# 08-DIPSwitches_I2C.net
KiCad netlist of a schematic drawn in Altium Designer
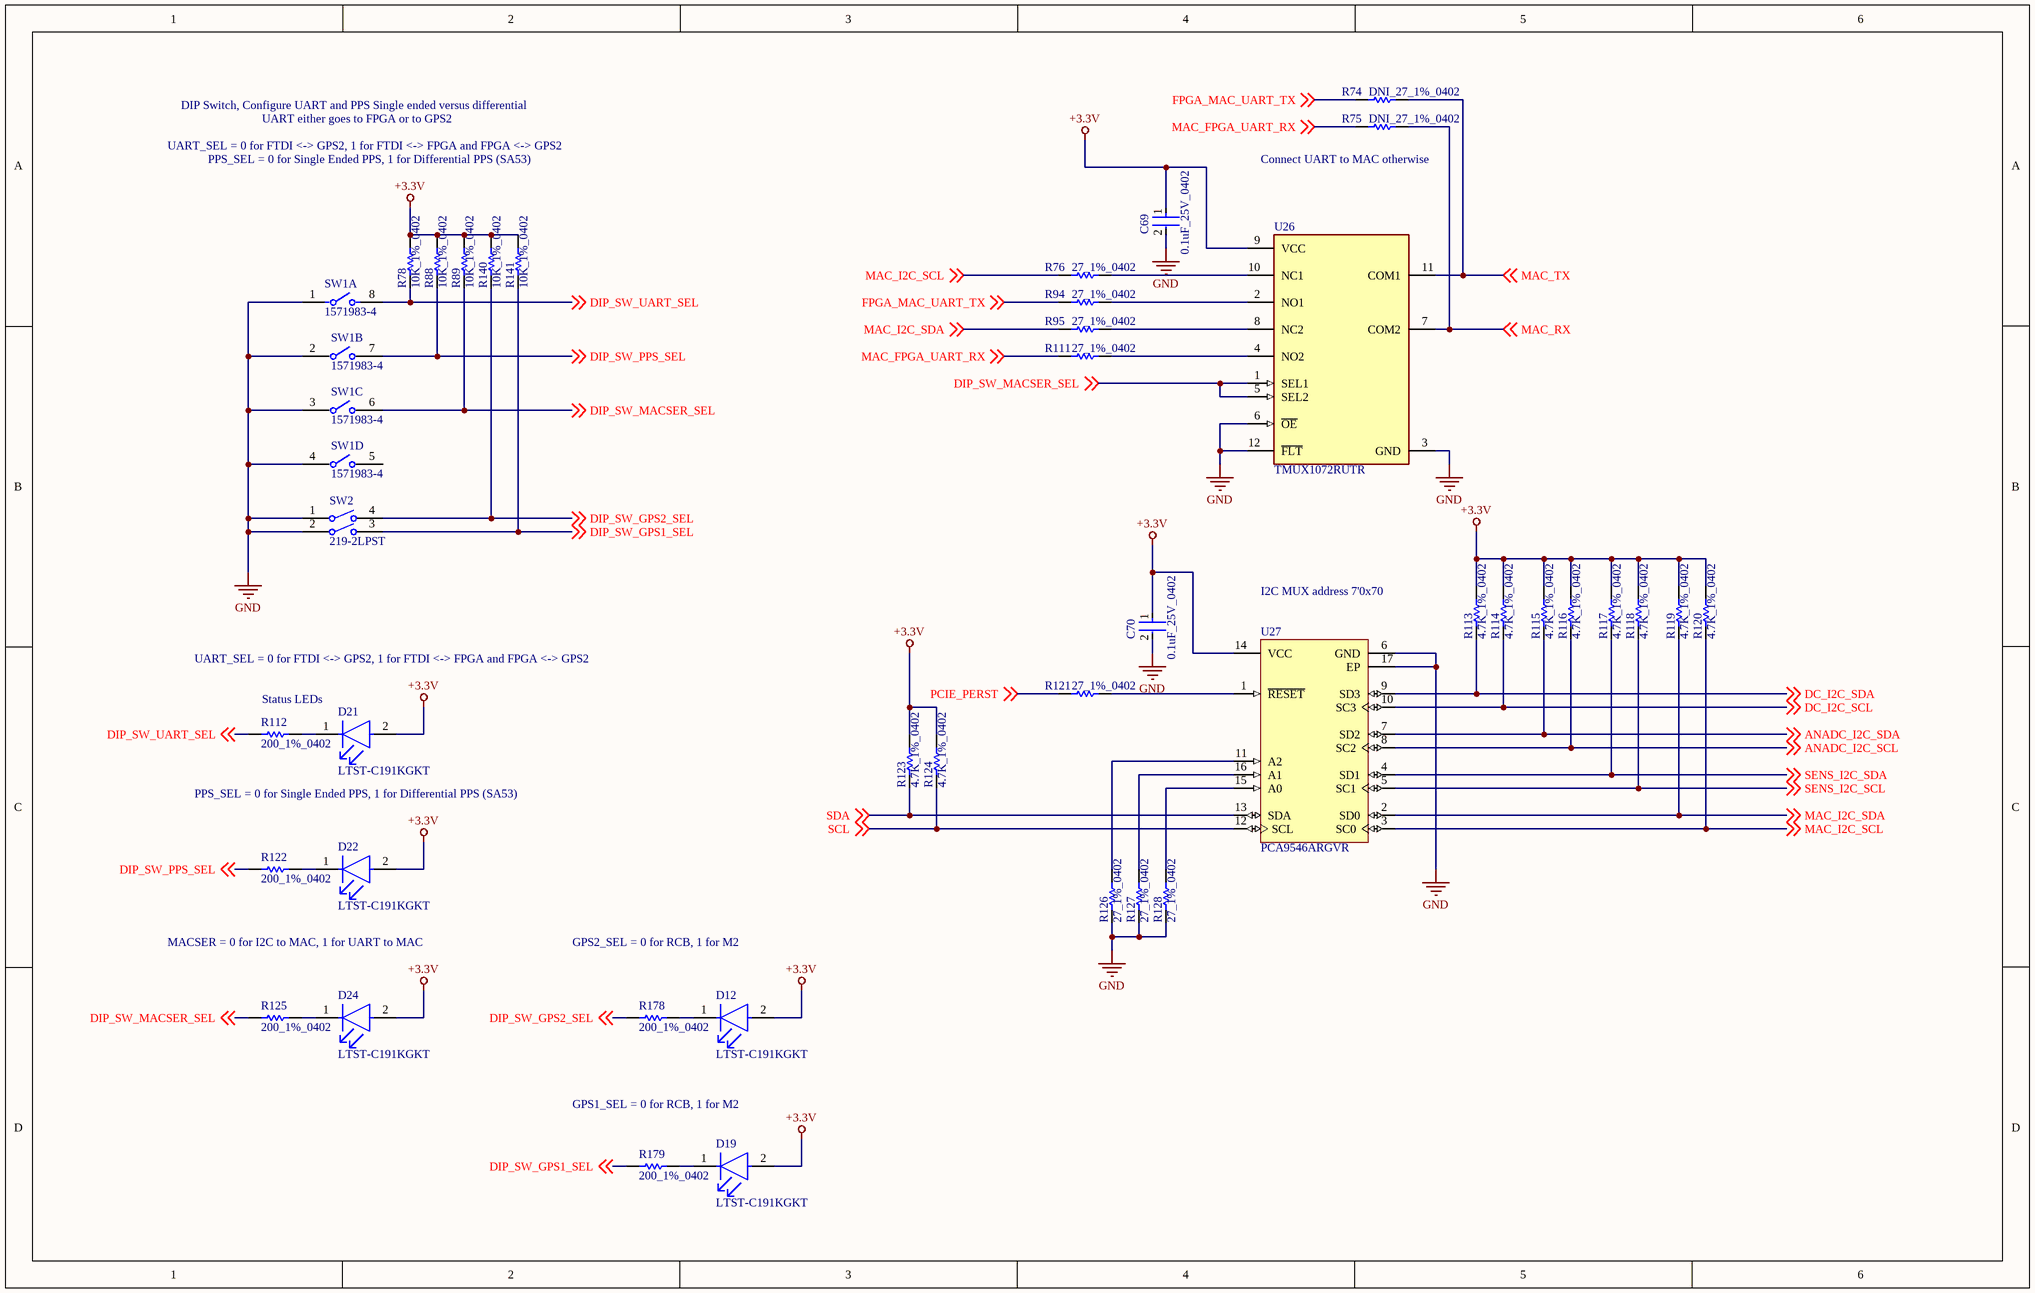
[diagram p0: 08-DIPSwitches_I2C.SchDoc]

(export (version "E")
  (design (tool "Eeschema 10.0.6"))
  (components
    (comp (ref "C69")
      (value "0.1uF_25V_0402")
      (footprint "FP-0402-L_1_0_1-W_0_5_0_1-IPC_C")
      (description "General Purpose Ceramic Capacitor, 0402, 100nF, 10%, X7R, 15%, 25V")
      (fields (field (name "VOLTAGE") "25V") (field (name "TOLERANCE") "10%"))
      (libsource (lib "Altium Content Vault") (part "b4654b650e69147ec39a6b967a45e02"))
    )
    (comp (ref "C70")
      (value "0.1uF_25V_0402")
      (footprint "FP-0402-L_1_0_1-W_0_5_0_1-IPC_C")
      (description "General Purpose Ceramic Capacitor, 0402, 100nF, 10%, X7R, 15%, 25V")
      (fields (field (name "VOLTAGE") "25V") (field (name "TOLERANCE") "10%"))
      (libsource (lib "Altium Content Vault") (part "b4654b650e69147ec39a6b967a45e02"))
    )
    (comp (ref "D12")
      (value "LTST-C191KGKT")
      (footprint "FP-LTST-C191KGKT-MFG")
      (description "LED GREEN CLEAR SMD")
      (libsource (lib "Altium Content Vault") (part "8706943c75ba83719d021d2fdc84c58"))
    )
    (comp (ref "D19")
      (value "LTST-C191KGKT")
      (footprint "FP-LTST-C191KGKT-MFG")
      (description "LED GREEN CLEAR SMD")
      (libsource (lib "Altium Content Vault") (part "8706943c75ba83719d021d2fdc84c58"))
    )
    (comp (ref "D21")
      (value "LTST-C191KGKT")
      (footprint "FP-LTST-C191KGKT-MFG")
      (description "LED GREEN CLEAR SMD")
      (libsource (lib "Altium Content Vault") (part "8706943c75ba83719d021d2fdc84c58"))
    )
    (comp (ref "D22")
      (value "LTST-C191KGKT")
      (footprint "FP-LTST-C191KGKT-MFG")
      (description "LED GREEN CLEAR SMD")
      (libsource (lib "Altium Content Vault") (part "8706943c75ba83719d021d2fdc84c58"))
    )
    (comp (ref "D24")
      (value "LTST-C191KGKT")
      (footprint "FP-LTST-C191KGKT-MFG")
      (description "LED GREEN CLEAR SMD")
      (libsource (lib "Altium Content Vault") (part "8706943c75ba83719d021d2fdc84c58"))
    )
    (comp (ref "R74")
      (value "DNI_27_1%_0402")
      (footprint "RESC1005X40X25NL05T05")
      (fields (field (name "PART NUMBER") "CRCW040227R0FKED") (field (name "MANUFACTURER") "Vishay Dale"))
      (libsource (lib "Altium Content Vault") (part "RES"))
    )
    (comp (ref "R75")
      (value "DNI_27_1%_0402")
      (footprint "RESC1005X40X25NL05T05")
      (fields (field (name "PART NUMBER") "CRCW040227R0FKED") (field (name "MANUFACTURER") "Vishay Dale"))
      (libsource (lib "Altium Content Vault") (part "RES"))
    )
    (comp (ref "R76")
      (value "27_1%_0402")
      (footprint "RESC1005X40X25NL05T05")
      (fields (field (name "PART NUMBER") "CRCW040227R0FKED") (field (name "MANUFACTURER") "Vishay Dale"))
      (libsource (lib "Altium Content Vault") (part "RES"))
    )
    (comp (ref "R78")
      (value "10K_1%_0402")
      (footprint "RESC1005X40X25LL05T10")
      (fields (field (name "PART NUMBER") "RC0402FR-0710KL") (field (name "MANUFACTURER") "Yageo / Phycomp"))
      (libsource (lib "Altium Content Vault") (part "RES"))
    )
    (comp (ref "R88")
      (value "10K_1%_0402")
      (footprint "RESC1005X40X25LL05T10")
      (fields (field (name "PART NUMBER") "RC0402FR-0710KL") (field (name "MANUFACTURER") "Yageo / Phycomp"))
      (libsource (lib "Altium Content Vault") (part "RES"))
    )
    (comp (ref "R89")
      (value "10K_1%_0402")
      (footprint "RESC1005X40X25LL05T10")
      (fields (field (name "PART NUMBER") "RC0402FR-0710KL") (field (name "MANUFACTURER") "Yageo / Phycomp"))
      (libsource (lib "Altium Content Vault") (part "RES"))
    )
    (comp (ref "R94")
      (value "27_1%_0402")
      (footprint "RESC1005X40X25NL05T05")
      (fields (field (name "PART NUMBER") "CRCW040227R0FKED") (field (name "MANUFACTURER") "Vishay Dale"))
      (libsource (lib "Altium Content Vault") (part "RES"))
    )
    (comp (ref "R95")
      (value "27_1%_0402")
      (footprint "RESC1005X40X25NL05T05")
      (fields (field (name "PART NUMBER") "CRCW040227R0FKED") (field (name "MANUFACTURER") "Vishay Dale"))
      (libsource (lib "Altium Content Vault") (part "RES"))
    )
    (comp (ref "R111")
      (value "27_1%_0402")
      (footprint "RESC1005X40X25NL05T05")
      (fields (field (name "PART NUMBER") "CRCW040227R0FKED") (field (name "MANUFACTURER") "Vishay Dale"))
      (libsource (lib "Altium Content Vault") (part "RES"))
    )
    (comp (ref "R112")
      (value "200_1%_0402")
      (footprint "RESC1005X40X25NL05T05")
      (fields (field (name "MANUFACTURER") "Vishay Dale") (field (name "PART NUMBER") "CRCW0402200RFKTD"))
      (libsource (lib "Altium Content Vault") (part "RES"))
    )
    (comp (ref "R113")
      (value "4.7K_1%_0402")
      (footprint "RESC1005X40X25NL10T10")
      (fields (field (name "MANUFACTURER") "Bourns") (field (name "PART NUMBER") "CR0402-FX-4701GLF"))
      (libsource (lib "Altium Content Vault") (part "RES"))
    )
    (comp (ref "R114")
      (value "4.7K_1%_0402")
      (footprint "RESC1005X40X25NL10T10")
      (fields (field (name "MANUFACTURER") "Bourns") (field (name "PART NUMBER") "CR0402-FX-4701GLF"))
      (libsource (lib "Altium Content Vault") (part "RES"))
    )
    (comp (ref "R115")
      (value "4.7K_1%_0402")
      (footprint "RESC1005X40X25NL10T10")
      (fields (field (name "MANUFACTURER") "Bourns") (field (name "PART NUMBER") "CR0402-FX-4701GLF"))
      (libsource (lib "Altium Content Vault") (part "RES"))
    )
    (comp (ref "R116")
      (value "4.7K_1%_0402")
      (footprint "RESC1005X40X25NL10T10")
      (fields (field (name "MANUFACTURER") "Bourns") (field (name "PART NUMBER") "CR0402-FX-4701GLF"))
      (libsource (lib "Altium Content Vault") (part "RES"))
    )
    (comp (ref "R117")
      (value "4.7K_1%_0402")
      (footprint "RESC1005X40X25NL10T10")
      (fields (field (name "MANUFACTURER") "Bourns") (field (name "PART NUMBER") "CR0402-FX-4701GLF"))
      (libsource (lib "Altium Content Vault") (part "RES"))
    )
    (comp (ref "R118")
      (value "4.7K_1%_0402")
      (footprint "RESC1005X40X25NL10T10")
      (fields (field (name "MANUFACTURER") "Bourns") (field (name "PART NUMBER") "CR0402-FX-4701GLF"))
      (libsource (lib "Altium Content Vault") (part "RES"))
    )
    (comp (ref "R119")
      (value "4.7K_1%_0402")
      (footprint "RESC1005X40X25NL10T10")
      (fields (field (name "MANUFACTURER") "Bourns") (field (name "PART NUMBER") "CR0402-FX-4701GLF"))
      (libsource (lib "Altium Content Vault") (part "RES"))
    )
    (comp (ref "R120")
      (value "4.7K_1%_0402")
      (footprint "RESC1005X40X25NL10T10")
      (fields (field (name "MANUFACTURER") "Bourns") (field (name "PART NUMBER") "CR0402-FX-4701GLF"))
      (libsource (lib "Altium Content Vault") (part "RES"))
    )
    (comp (ref "R121")
      (value "27_1%_0402")
      (footprint "RESC1005X40X25NL05T05")
      (fields (field (name "PART NUMBER") "CRCW040227R0FKED") (field (name "MANUFACTURER") "Vishay Dale"))
      (libsource (lib "Altium Content Vault") (part "RES"))
    )
    (comp (ref "R122")
      (value "200_1%_0402")
      (footprint "RESC1005X40X25NL05T05")
      (fields (field (name "MANUFACTURER") "Vishay Dale") (field (name "PART NUMBER") "CRCW0402200RFKTD"))
      (libsource (lib "Altium Content Vault") (part "RES"))
    )
    (comp (ref "R123")
      (value "4.7K_1%_0402")
      (footprint "RESC1005X40X25NL10T10")
      (fields (field (name "MANUFACTURER") "Bourns") (field (name "PART NUMBER") "CR0402-FX-4701GLF"))
      (libsource (lib "Altium Content Vault") (part "RES"))
    )
    (comp (ref "R124")
      (value "4.7K_1%_0402")
      (footprint "RESC1005X40X25NL10T10")
      (fields (field (name "MANUFACTURER") "Bourns") (field (name "PART NUMBER") "CR0402-FX-4701GLF"))
      (libsource (lib "Altium Content Vault") (part "RES"))
    )
    (comp (ref "R125")
      (value "200_1%_0402")
      (footprint "RESC1005X40X25NL05T05")
      (fields (field (name "MANUFACTURER") "Vishay Dale") (field (name "PART NUMBER") "CRCW0402200RFKTD"))
      (libsource (lib "Altium Content Vault") (part "RES"))
    )
    (comp (ref "R126")
      (value "27_1%_0402")
      (footprint "RESC1005X40X25NL05T05")
      (fields (field (name "PART NUMBER") "CRCW040227R0FKED") (field (name "MANUFACTURER") "Vishay Dale"))
      (libsource (lib "Altium Content Vault") (part "RES"))
    )
    (comp (ref "R127")
      (value "27_1%_0402")
      (footprint "RESC1005X40X25NL05T05")
      (fields (field (name "PART NUMBER") "CRCW040227R0FKED") (field (name "MANUFACTURER") "Vishay Dale"))
      (libsource (lib "Altium Content Vault") (part "RES"))
    )
    (comp (ref "R128")
      (value "27_1%_0402")
      (footprint "RESC1005X40X25NL05T05")
      (fields (field (name "PART NUMBER") "CRCW040227R0FKED") (field (name "MANUFACTURER") "Vishay Dale"))
      (libsource (lib "Altium Content Vault") (part "RES"))
    )
    (comp (ref "R140")
      (value "10K_1%_0402")
      (footprint "RESC1005X40X25LL05T10")
      (fields (field (name "PART NUMBER") "RC0402FR-0710KL") (field (name "MANUFACTURER") "Yageo / Phycomp"))
      (libsource (lib "Altium Content Vault") (part "RES"))
    )
    (comp (ref "R141")
      (value "10K_1%_0402")
      (footprint "RESC1005X40X25LL05T10")
      (fields (field (name "PART NUMBER") "RC0402FR-0710KL") (field (name "MANUFACTURER") "Yageo / Phycomp"))
      (libsource (lib "Altium Content Vault") (part "RES"))
    )
    (comp (ref "R178")
      (value "200_1%_0402")
      (footprint "RESC1005X40X25NL05T05")
      (fields (field (name "MANUFACTURER") "Vishay Dale") (field (name "PART NUMBER") "CRCW0402200RFKTD"))
      (libsource (lib "Altium Content Vault") (part "RES"))
    )
    (comp (ref "R179")
      (value "200_1%_0402")
      (footprint "RESC1005X40X25NL05T05")
      (fields (field (name "MANUFACTURER") "Vishay Dale") (field (name "PART NUMBER") "CRCW0402200RFKTD"))
      (libsource (lib "Altium Content Vault") (part "RES"))
    )
    (comp (ref "SW1")
      (value "1571983-4")
      (footprint "FP-1571983-4-MFG")
      (description "SWITCH SLIDE DIP SPST 25MA 24V")
      (fields
        (field (name "OCTOPART") "https://octopart.com/1571983-4-te+connectivity-46507521")
        (field (name "MANUFACTURER") "TE Connectivity")
      )
      (libsource (lib "Altium Content Vault") (part "6123b3bffd52fd60b6df23d79e332fa"))
    )
    (comp (ref "SW2")
      (value "219-2LPST")
      (footprint "CTS-219-2LPST_V")
      (description "Surface Mount DIP Switch Auto Placeable, -55 to 85 degC, 4-Pin SMD, RoHS, Tube")
      (fields (field (name "MANUFACTURER") "CTS Corporation"))
      (libsource (lib "Altium Content Vault") (part "SW-SPST-4_C"))
    )
    (comp (ref "U26")
      (value "TMUX1072RUTR")
      (footprint "FP-RUT0012A-MFG")
      (description "IC SWITCH SPDT DUAL 12UQFN")
      (libsource (lib "Altium Content Vault") (part "12a319ab100cd6cfe745e35972674f5"))
    )
    (comp (ref "U27")
      (value "PCA9546ARGVR")
      (footprint "RGV0016A_V")
      (fields (field (name "MANUFACTURER") "Texas Instruments"))
      (libsource (lib "Altium Content Vault") (part "TI-PCA9546A-VQFN_RGV-16"))
    )
  )
  (nets
    (net (code "1") (name "+3.3V") (class "Default")
      (node (ref "C69") (pin "1") (pinfunction "1_1") (pintype "passive"))
      (node (ref "C70") (pin "1") (pinfunction "1_1") (pintype "passive"))
      (node (ref "D12") (pin "2") (pinfunction "A_2") (pintype "passive"))
      (node (ref "D19") (pin "2") (pinfunction "A_2") (pintype "passive"))
      (node (ref "D21") (pin "2") (pinfunction "A_2") (pintype "passive"))
      (node (ref "D22") (pin "2") (pinfunction "A_2") (pintype "passive"))
      (node (ref "D24") (pin "2") (pinfunction "A_2") (pintype "passive"))
      (node (ref "R113") (pin "2") (pinfunction "2_2") (pintype "passive"))
      (node (ref "R114") (pin "2") (pinfunction "2_2") (pintype "passive"))
      (node (ref "R115") (pin "2") (pinfunction "2_2") (pintype "passive"))
      (node (ref "R116") (pin "2") (pinfunction "2_2") (pintype "passive"))
      (node (ref "R117") (pin "2") (pinfunction "2_2") (pintype "passive"))
      (node (ref "R118") (pin "2") (pinfunction "2_2") (pintype "passive"))
      (node (ref "R119") (pin "2") (pinfunction "2_2") (pintype "passive"))
      (node (ref "R120") (pin "2") (pinfunction "2_2") (pintype "passive"))
      (node (ref "R123") (pin "2") (pinfunction "2_2") (pintype "passive"))
      (node (ref "R124") (pin "2") (pinfunction "2_2") (pintype "passive"))
      (node (ref "R140") (pin "1") (pinfunction "1_1") (pintype "passive"))
      (node (ref "R141") (pin "1") (pinfunction "1_1") (pintype "passive"))
      (node (ref "R78") (pin "1") (pinfunction "1_1") (pintype "passive"))
      (node (ref "R88") (pin "1") (pinfunction "1_1") (pintype "passive"))
      (node (ref "R89") (pin "1") (pinfunction "1_1") (pintype "passive"))
      (node (ref "U26") (pin "9") (pinfunction "VCC_9") (pintype "power_in"))
      (node (ref "U27") (pin "14") (pinfunction "VCC_14") (pintype "power_in"))
    )
    (net (code "2") (name "ANADC_I2C_SCL") (class "Default")
      (node (ref "R116") (pin "1") (pinfunction "1_1") (pintype "passive"))
      (node (ref "U27") (pin "8") (pinfunction "SC2_8") (pintype "bidirectional"))
    )
    (net (code "3") (name "ANADC_I2C_SDA") (class "Default")
      (node (ref "R115") (pin "1") (pinfunction "1_1") (pintype "passive"))
      (node (ref "U27") (pin "7") (pinfunction "SD2_7") (pintype "bidirectional"))
    )
    (net (code "4") (name "DC_I2C_SCL") (class "Default")
      (node (ref "R114") (pin "1") (pinfunction "1_1") (pintype "passive"))
      (node (ref "U27") (pin "10") (pinfunction "SC3_10") (pintype "bidirectional"))
    )
    (net (code "5") (name "DC_I2C_SDA") (class "Default")
      (node (ref "R113") (pin "1") (pinfunction "1_1") (pintype "passive"))
      (node (ref "U27") (pin "9") (pinfunction "SD3_9") (pintype "bidirectional"))
    )
    (net (code "6") (name "DIP_SW_GPS1_SEL") (class "Default")
      (node (ref "R141") (pin "2") (pinfunction "2_2") (pintype "passive"))
      (node (ref "R179") (pin "2") (pinfunction "2_2") (pintype "passive"))
      (node (ref "SW2") (pin "3") (pinfunction "3_3") (pintype "passive"))
    )
    (net (code "7") (name "DIP_SW_GPS2_SEL") (class "Default")
      (node (ref "R140") (pin "2") (pinfunction "2_2") (pintype "passive"))
      (node (ref "R178") (pin "2") (pinfunction "2_2") (pintype "passive"))
      (node (ref "SW2") (pin "4") (pinfunction "4_4") (pintype "passive"))
    )
    (net (code "8") (name "DIP_SW_MACSER_SEL") (class "Default")
      (node (ref "R125") (pin "2") (pinfunction "2_2") (pintype "passive"))
      (node (ref "R89") (pin "2") (pinfunction "2_2") (pintype "passive"))
      (node (ref "SW1") (pin "6") (pinfunction "6_6") (pintype "passive"))
      (node (ref "U26") (pin "1") (pinfunction "SEL1_1") (pintype "input"))
      (node (ref "U26") (pin "5") (pinfunction "SEL2_5") (pintype "input"))
    )
    (net (code "9") (name "DIP_SW_PPS_SEL") (class "Default")
      (node (ref "R122") (pin "2") (pinfunction "2_2") (pintype "passive"))
      (node (ref "R88") (pin "2") (pinfunction "2_2") (pintype "passive"))
      (node (ref "SW1") (pin "7") (pinfunction "7_7") (pintype "passive"))
    )
    (net (code "10") (name "DIP_SW_UART_SEL") (class "Default")
      (node (ref "R112") (pin "2") (pinfunction "2_2") (pintype "passive"))
      (node (ref "R78") (pin "2") (pinfunction "2_2") (pintype "passive"))
      (node (ref "SW1") (pin "8") (pinfunction "8_8") (pintype "passive"))
    )
    (net (code "11") (name "FPGA_MAC_UART_TX") (class "Default")
      (node (ref "R74") (pin "1") (pinfunction "1_1") (pintype "passive"))
      (node (ref "R94") (pin "1") (pinfunction "1_1") (pintype "passive"))
    )
    (net (code "12") (name "GND") (class "Default")
      (node (ref "C69") (pin "2") (pinfunction "2_2") (pintype "passive"))
      (node (ref "C70") (pin "2") (pinfunction "2_2") (pintype "passive"))
      (node (ref "R126") (pin "1") (pinfunction "1_1") (pintype "passive"))
      (node (ref "R127") (pin "1") (pinfunction "1_1") (pintype "passive"))
      (node (ref "R128") (pin "1") (pinfunction "1_1") (pintype "passive"))
      (node (ref "SW1") (pin "1") (pinfunction "1_1") (pintype "passive"))
      (node (ref "SW1") (pin "2") (pinfunction "2_2") (pintype "passive"))
      (node (ref "SW1") (pin "3") (pinfunction "3_3") (pintype "passive"))
      (node (ref "SW1") (pin "4") (pinfunction "4_4") (pintype "passive"))
      (node (ref "SW2") (pin "1") (pinfunction "1_1") (pintype "passive"))
      (node (ref "SW2") (pin "2") (pinfunction "2_2") (pintype "passive"))
      (node (ref "U26") (pin "12") (pinfunction "~{FLT}_12") (pintype "open_collector"))
      (node (ref "U26") (pin "3") (pinfunction "GND_3") (pintype "power_in"))
      (node (ref "U26") (pin "6") (pinfunction "~{OE}_6") (pintype "input"))
      (node (ref "U27") (pin "17") (pinfunction "EP_17") (pintype "passive"))
      (node (ref "U27") (pin "6") (pinfunction "GND_6") (pintype "power_in"))
    )
    (net (code "13") (name "MAC_FPGA_UART_RX") (class "Default")
      (node (ref "R111") (pin "1") (pinfunction "1_1") (pintype "passive"))
      (node (ref "R75") (pin "1") (pinfunction "1_1") (pintype "passive"))
    )
    (net (code "14") (name "MAC_I2C_SCL") (class "Default")
      (node (ref "R120") (pin "1") (pinfunction "1_1") (pintype "passive"))
      (node (ref "R76") (pin "1") (pinfunction "1_1") (pintype "passive"))
      (node (ref "U27") (pin "3") (pinfunction "SC0_3") (pintype "bidirectional"))
    )
    (net (code "15") (name "MAC_I2C_SDA") (class "Default")
      (node (ref "R119") (pin "1") (pinfunction "1_1") (pintype "passive"))
      (node (ref "R95") (pin "1") (pinfunction "1_1") (pintype "passive"))
      (node (ref "U27") (pin "2") (pinfunction "SD0_2") (pintype "bidirectional"))
    )
    (net (code "16") (name "MAC_RX") (class "Default")
      (node (ref "R75") (pin "2") (pinfunction "2_2") (pintype "passive"))
      (node (ref "U26") (pin "7") (pinfunction "COM2_7") (pintype "passive"))
    )
    (net (code "17") (name "MAC_TX") (class "Default")
      (node (ref "R74") (pin "2") (pinfunction "2_2") (pintype "passive"))
      (node (ref "U26") (pin "11") (pinfunction "COM1_11") (pintype "passive"))
    )
    (net (code "18") (name "Net-(D12-C)") (class "Default")
      (node (ref "D12") (pin "1") (pinfunction "C_1") (pintype "passive"))
      (node (ref "R178") (pin "1") (pinfunction "1_1") (pintype "passive"))
    )
    (net (code "19") (name "Net-(D19-C)") (class "Default")
      (node (ref "D19") (pin "1") (pinfunction "C_1") (pintype "passive"))
      (node (ref "R179") (pin "1") (pinfunction "1_1") (pintype "passive"))
    )
    (net (code "20") (name "Net-(D21-C)") (class "Default")
      (node (ref "D21") (pin "1") (pinfunction "C_1") (pintype "passive"))
      (node (ref "R112") (pin "1") (pinfunction "1_1") (pintype "passive"))
    )
    (net (code "21") (name "Net-(D22-C)") (class "Default")
      (node (ref "D22") (pin "1") (pinfunction "C_1") (pintype "passive"))
      (node (ref "R122") (pin "1") (pinfunction "1_1") (pintype "passive"))
    )
    (net (code "22") (name "Net-(D24-C)") (class "Default")
      (node (ref "D24") (pin "1") (pinfunction "C_1") (pintype "passive"))
      (node (ref "R125") (pin "1") (pinfunction "1_1") (pintype "passive"))
    )
    (net (code "23") (name "Net-(U26-NC1)") (class "Default")
      (node (ref "R76") (pin "2") (pinfunction "2_2") (pintype "passive"))
      (node (ref "U26") (pin "10") (pinfunction "NC1_10") (pintype "passive"))
    )
    (net (code "24") (name "Net-(U26-NC2)") (class "Default")
      (node (ref "R95") (pin "2") (pinfunction "2_2") (pintype "passive"))
      (node (ref "U26") (pin "8") (pinfunction "NC2_8") (pintype "passive"))
    )
    (net (code "25") (name "Net-(U26-NO1)") (class "Default")
      (node (ref "R94") (pin "2") (pinfunction "2_2") (pintype "passive"))
      (node (ref "U26") (pin "2") (pinfunction "NO1_2") (pintype "passive"))
    )
    (net (code "26") (name "Net-(U26-NO2)") (class "Default")
      (node (ref "R111") (pin "2") (pinfunction "2_2") (pintype "passive"))
      (node (ref "U26") (pin "4") (pinfunction "NO2_4") (pintype "passive"))
    )
    (net (code "27") (name "Net-(U27-A0)") (class "Default")
      (node (ref "R128") (pin "2") (pinfunction "2_2") (pintype "passive"))
      (node (ref "U27") (pin "15") (pinfunction "A0_15") (pintype "input"))
    )
    (net (code "28") (name "Net-(U27-A1)") (class "Default")
      (node (ref "R127") (pin "2") (pinfunction "2_2") (pintype "passive"))
      (node (ref "U27") (pin "16") (pinfunction "A1_16") (pintype "input"))
    )
    (net (code "29") (name "Net-(U27-A2)") (class "Default")
      (node (ref "R126") (pin "2") (pinfunction "2_2") (pintype "passive"))
      (node (ref "U27") (pin "11") (pinfunction "A2_11") (pintype "input"))
    )
    (net (code "30") (name "Net-(U27-~{RESET})") (class "Default")
      (node (ref "R121") (pin "2") (pinfunction "2_2") (pintype "passive"))
      (node (ref "U27") (pin "1") (pinfunction "~{RESET}_1") (pintype "input"))
    )
    (net (code "31") (name "PCIE_PERST") (class "Default")
      (node (ref "R121") (pin "1") (pinfunction "1_1") (pintype "passive"))
    )
    (net (code "32") (name "SCL") (class "Default")
      (node (ref "R124") (pin "1") (pinfunction "1_1") (pintype "passive"))
      (node (ref "U27") (pin "12") (pinfunction "SCL_12") (pintype "bidirectional"))
    )
    (net (code "33") (name "SDA") (class "Default")
      (node (ref "R123") (pin "1") (pinfunction "1_1") (pintype "passive"))
      (node (ref "U27") (pin "13") (pinfunction "SDA_13") (pintype "bidirectional"))
    )
    (net (code "34") (name "SENS_I2C_SCL") (class "Default")
      (node (ref "R118") (pin "1") (pinfunction "1_1") (pintype "passive"))
      (node (ref "U27") (pin "5") (pinfunction "SC1_5") (pintype "bidirectional"))
    )
    (net (code "35") (name "SENS_I2C_SDA") (class "Default")
      (node (ref "R117") (pin "1") (pinfunction "1_1") (pintype "passive"))
      (node (ref "U27") (pin "4") (pinfunction "SD1_4") (pintype "bidirectional"))
    )
    (net (code "36") (name "unconnected-(SW1-Pad5)") (class "Default")
      (node (ref "SW1") (pin "5") (pinfunction "5_5") (pintype "passive"))
    )
  )
)
